# ATTiny13_ISPProgrammer.net
KiCad netlist of a schematic drawn in EAGLE
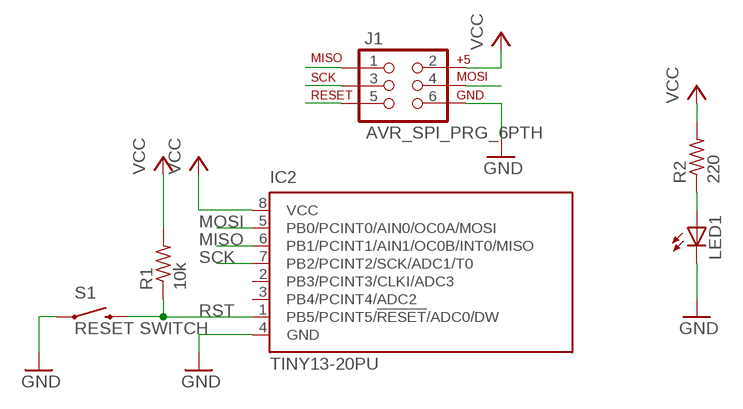
[diagram p0: schematic, sheet 1]

(export (version "E")
  (design (tool "Eeschema 10.0.6"))
  (components
    (comp (ref "IC2")
      (value "TINY13-20PU")
      (footprint "eagle-import:DIL08")
      (fields (field (name "MPN") "ATTINY13-20PU"))
      (libsource (lib "eagle-import") (part "TINY13PU-20"))
    )
    (comp (ref "J1")
      (value "AVR_SPI_PRG_6PTH")
      (footprint "eagle-import:2X3")
      (libsource (lib "eagle-import") (part "AVR_SPI_PRG_6PTH"))
    )
    (comp (ref "LED1")
      (value "LED-3MM-NO_SILK")
      (footprint "eagle-import:LED3MM-NS")
      (libsource (lib "eagle-import") (part "LED-3MM-NO_SILK"))
    )
    (comp (ref "R1")
      (value "10k")
      (footprint "eagle-import:0207_10")
      (libsource (lib "eagle-import") (part "R-US_0207/10"))
    )
    (comp (ref "R2")
      (value "220")
      (footprint "eagle-import:0207_10")
      (libsource (lib "eagle-import") (part "R-US_0207/10"))
    )
    (comp (ref "S1")
      (value "RESET SWITCH")
      (footprint "eagle-import:TACTILE-PTH")
      (libsource (lib "eagle-import") (part "SWITCH-MOMENTARY-2PTH"))
    )
  )
  (nets
    (net (code "1") (name "/MISO") (class "Default")
      (node (ref "IC2") (pin "6") (pinfunction "PB1/PCINT1/AIN1/OC0B/INT0/MISO_6") (pintype "bidirectional"))
      (node (ref "J1") (pin "1") (pinfunction "1_1") (pintype "passive"))
    )
    (net (code "2") (name "/MOSI") (class "Default")
      (node (ref "IC2") (pin "5") (pinfunction "PB0/PCINT0/AIN0/OC0A/MOSI_5") (pintype "bidirectional"))
      (node (ref "J1") (pin "4") (pinfunction "4_4") (pintype "passive"))
    )
    (net (code "3") (name "/RST") (class "Default")
      (node (ref "IC2") (pin "1") (pinfunction "PB5/PCINT5/~{RESET}/ADC0/DW_1") (pintype "bidirectional"))
      (node (ref "J1") (pin "5") (pinfunction "5_5") (pintype "passive"))
      (node (ref "R1") (pin "1") (pinfunction "1_1") (pintype "passive"))
      (node (ref "S1") (pin "3") (pinfunction "2_3") (pintype "passive"))
    )
    (net (code "4") (name "/SCK") (class "Default")
      (node (ref "IC2") (pin "7") (pinfunction "PB2/PCINT2/SCK/ADC1/T0_7") (pintype "bidirectional"))
      (node (ref "J1") (pin "3") (pinfunction "3_3") (pintype "passive"))
    )
    (net (code "5") (name "GND") (class "Default")
      (node (ref "IC2") (pin "4") (pinfunction "GND_4") (pintype "power_in"))
      (node (ref "J1") (pin "6") (pinfunction "6_6") (pintype "passive"))
      (node (ref "LED1") (pin "K") (pinfunction "C_K") (pintype "passive"))
      (node (ref "S1") (pin "1") (pinfunction "1_1") (pintype "passive"))
    )
    (net (code "6") (name "Net-(LED1-PadA)") (class "Default")
      (node (ref "LED1") (pin "A") (pinfunction "A_A") (pintype "passive"))
      (node (ref "R2") (pin "1") (pinfunction "1_1") (pintype "passive"))
    )
    (net (code "7") (name "VCC") (class "Default")
      (node (ref "IC2") (pin "8") (pinfunction "VCC_8") (pintype "power_in"))
      (node (ref "J1") (pin "2") (pinfunction "2_2") (pintype "passive"))
      (node (ref "R1") (pin "2") (pinfunction "2_2") (pintype "passive"))
      (node (ref "R2") (pin "2") (pinfunction "2_2") (pintype "passive"))
    )
    (net (code "8") (name "unconnected-(IC2-PB3{slash}PCINT3{slash}CLKI{slash}ADC3-Pad2)") (class "Default")
      (node (ref "IC2") (pin "2") (pinfunction "PB3/PCINT3/CLKI/ADC3_2") (pintype "bidirectional"))
    )
    (net (code "9") (name "unconnected-(IC2-PB4{slash}PCINT4{slash}ADC2-Pad3)") (class "Default")
      (node (ref "IC2") (pin "3") (pinfunction "PB4/PCINT4/ADC2_3") (pintype "bidirectional"))
    )
  )
)
